# LightLog_SMD_0_7.net
KiCad netlist of a schematic drawn in EAGLE
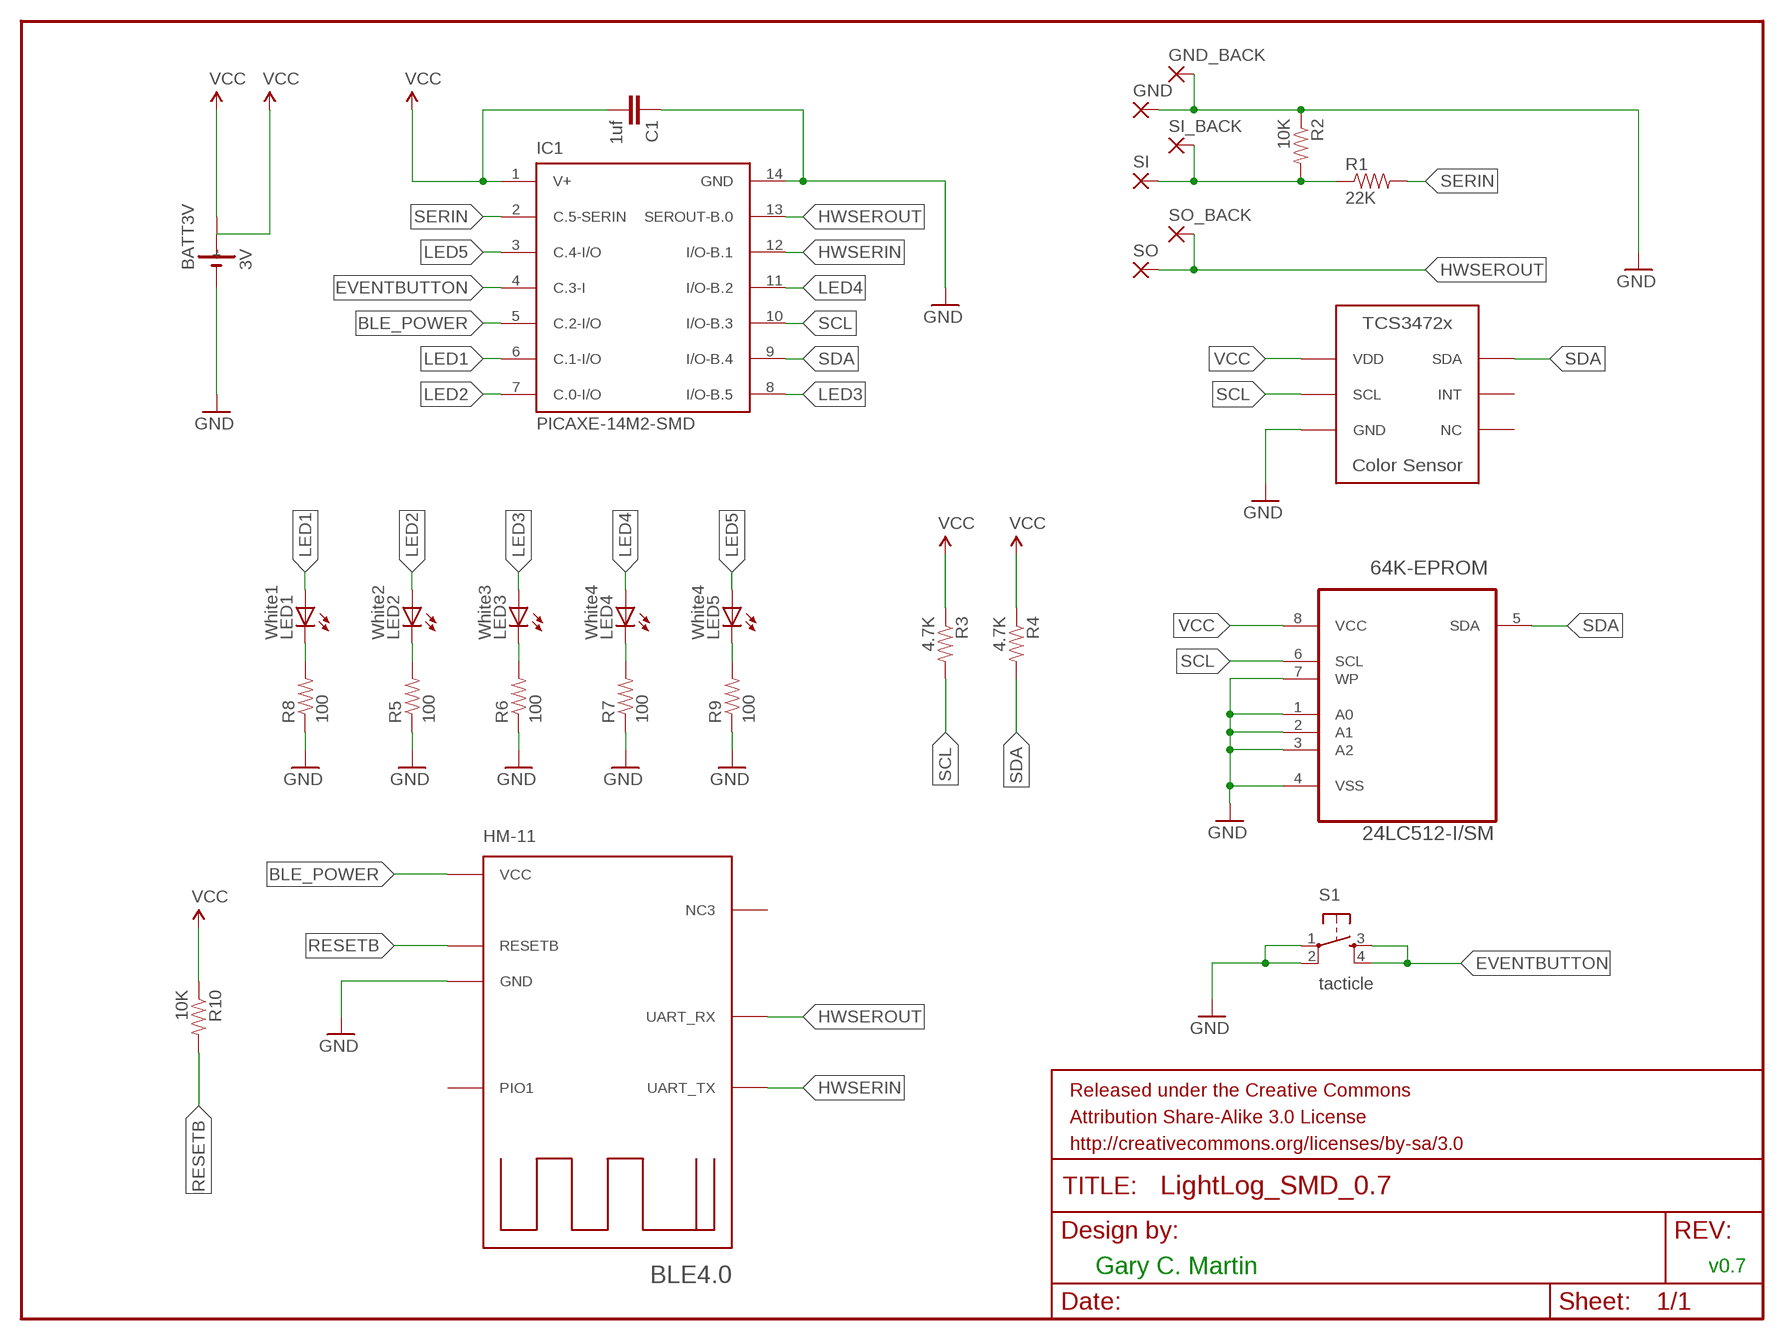
[diagram p0: schematic, sheet 1]

(export (version "E")
  (design (tool "Eeschema 10.0.6"))
  (components
    (comp (ref "64K-EPROM")
      (value "24LC512-I/SM")
      (footprint "eagle-import:SOIC127P794X203-8N")
      (libsource (lib "eagle-import") (part "24LC512-I/SM"))
    )
    (comp (ref "BATT3V")
      (value "3V")
      (footprint "eagle-import:BAT-HLD-001-CR2032-SMD")
      (libsource (lib "eagle-import") (part "BAT-HLD-001-CR2032"))
    )
    (comp (ref "BLE4.0")
      (value "HM-11")
      (footprint "eagle-import:HM-11-MIN")
      (libsource (lib "eagle-import") (part "HM-11-MIN"))
    )
    (comp (ref "C1")
      (value "1uf")
      (footprint "eagle-import:0805")
      (libsource (lib "eagle-import") (part "CAP0805"))
    )
    (comp (ref "GND")
      (value "SMD2")
      (footprint "eagle-import:SMD1,27-2,54")
      (libsource (lib "eagle-import") (part "SMD2"))
    )
    (comp (ref "GND_BACK")
      (value "SMD2")
      (footprint "eagle-import:SMD1,27-2,54")
      (libsource (lib "eagle-import") (part "SMD2"))
    )
    (comp (ref "IC1")
      (value "PICAXE-14M2-SMD")
      (footprint "eagle-import:SOIC14")
      (libsource (lib "eagle-import") (part "PICAXE-14M2-SMD"))
    )
    (comp (ref "LED1")
      (value "White1")
      (footprint "eagle-import:LED-0603")
      (libsource (lib "eagle-import") (part "LED0603"))
    )
    (comp (ref "LED2")
      (value "White2")
      (footprint "eagle-import:LED-0603")
      (libsource (lib "eagle-import") (part "LED0603"))
    )
    (comp (ref "LED3")
      (value "White3")
      (footprint "eagle-import:LED-0603")
      (libsource (lib "eagle-import") (part "LED0603"))
    )
    (comp (ref "LED4")
      (value "White4")
      (footprint "eagle-import:LED-0603")
      (libsource (lib "eagle-import") (part "LED0603"))
    )
    (comp (ref "LED5")
      (value "White4")
      (footprint "eagle-import:LED-0603")
      (libsource (lib "eagle-import") (part "LED0603"))
    )
    (comp (ref "R1")
      (value "22K")
      (footprint "eagle-import:0805")
      (libsource (lib "eagle-import") (part "RESISTOR0805-RES"))
    )
    (comp (ref "R2")
      (value "10K")
      (footprint "eagle-import:0805")
      (libsource (lib "eagle-import") (part "RESISTOR0805-RES"))
    )
    (comp (ref "R3")
      (value "4.7K")
      (footprint "eagle-import:0805")
      (libsource (lib "eagle-import") (part "RESISTOR0805-RES"))
    )
    (comp (ref "R4")
      (value "4.7K")
      (footprint "eagle-import:0805")
      (libsource (lib "eagle-import") (part "RESISTOR0805-RES"))
    )
    (comp (ref "R5")
      (value "100")
      (footprint "eagle-import:0805")
      (libsource (lib "eagle-import") (part "RESISTOR0805-RES"))
    )
    (comp (ref "R6")
      (value "100")
      (footprint "eagle-import:0805")
      (libsource (lib "eagle-import") (part "RESISTOR0805-RES"))
    )
    (comp (ref "R7")
      (value "100")
      (footprint "eagle-import:0805")
      (libsource (lib "eagle-import") (part "RESISTOR0805-RES"))
    )
    (comp (ref "R8")
      (value "100")
      (footprint "eagle-import:0805")
      (libsource (lib "eagle-import") (part "RESISTOR0805-RES"))
    )
    (comp (ref "R9")
      (value "100")
      (footprint "eagle-import:0805")
      (libsource (lib "eagle-import") (part "RESISTOR0805-RES"))
    )
    (comp (ref "R10")
      (value "10K")
      (footprint "eagle-import:0805")
      (libsource (lib "eagle-import") (part "RESISTOR0805-RES"))
    )
    (comp (ref "S1")
      (value "tacticle")
      (footprint "eagle-import:TACTILE_SWITCH_SMD")
      (libsource (lib "eagle-import") (part "TAC_SWITCHSMD"))
    )
    (comp (ref "SI")
      (value "SMD2")
      (footprint "eagle-import:SMD1,27-2,54")
      (libsource (lib "eagle-import") (part "SMD2"))
    )
    (comp (ref "SI_BACK")
      (value "SMD2")
      (footprint "eagle-import:SMD1,27-2,54")
      (libsource (lib "eagle-import") (part "SMD2"))
    )
    (comp (ref "SO")
      (value "SMD2")
      (footprint "eagle-import:SMD1,27-2,54")
      (libsource (lib "eagle-import") (part "SMD2"))
    )
    (comp (ref "SO_BACK")
      (value "SMD2")
      (footprint "eagle-import:SMD1,27-2,54")
      (libsource (lib "eagle-import") (part "SMD2"))
    )
    (comp (ref "U$1")
      (value "TCS3472")
      (footprint "eagle-import:DUAL-FLAT-NO-LEAD-6PIN")
      (libsource (lib "eagle-import") (part "TCS3472"))
    )
  )
  (nets
    (net (code "1") (name "BLE_POWER") (class "Default")
      (node (ref "BLE4.0") (pin "VCC") (pinfunction "VCC_VCC") (pintype "bidirectional"))
      (node (ref "IC1") (pin "5") (pinfunction "C.2-I/O_5") (pintype "bidirectional"))
    )
    (net (code "2") (name "EVENTBUTTON") (class "Default")
      (node (ref "IC1") (pin "4") (pinfunction "C.3-I_4") (pintype "input"))
      (node (ref "S1") (pin "3") (pinfunction "3_3") (pintype "passive"))
      (node (ref "S1") (pin "4") (pinfunction "4_4") (pintype "passive"))
    )
    (net (code "3") (name "GND") (class "Default")
      (node (ref "64K-EPROM") (pin "1") (pinfunction "A0_1") (pintype "input"))
      (node (ref "64K-EPROM") (pin "2") (pinfunction "A1_2") (pintype "input"))
      (node (ref "64K-EPROM") (pin "3") (pinfunction "A2_3") (pintype "input"))
      (node (ref "64K-EPROM") (pin "4") (pinfunction "VSS_4") (pintype "passive"))
      (node (ref "64K-EPROM") (pin "7") (pinfunction "WP_7") (pintype "input"))
      (node (ref "BATT3V") (pin "NEG") (pinfunction "-_NEG") (pintype "passive"))
      (node (ref "BLE4.0") (pin "GND") (pinfunction "GND_GND") (pintype "bidirectional"))
      (node (ref "C1") (pin "1") (pinfunction "1_1") (pintype "passive"))
      (node (ref "GND") (pin "1") (pinfunction "P_1") (pintype "passive"))
      (node (ref "GND_BACK") (pin "1") (pinfunction "P_1") (pintype "passive"))
      (node (ref "IC1") (pin "14") (pinfunction "GND_14") (pintype "power_in"))
      (node (ref "R2") (pin "1") (pinfunction "1_1") (pintype "passive"))
      (node (ref "R5") (pin "1") (pinfunction "1_1") (pintype "passive"))
      (node (ref "R6") (pin "1") (pinfunction "1_1") (pintype "passive"))
      (node (ref "R7") (pin "1") (pinfunction "1_1") (pintype "passive"))
      (node (ref "R8") (pin "1") (pinfunction "1_1") (pintype "passive"))
      (node (ref "R9") (pin "1") (pinfunction "1_1") (pintype "passive"))
      (node (ref "S1") (pin "1") (pinfunction "1_1") (pintype "passive"))
      (node (ref "S1") (pin "2") (pinfunction "2_2") (pintype "passive"))
      (node (ref "U$1") (pin "3") (pinfunction "GND_3") (pintype "bidirectional"))
    )
    (net (code "4") (name "HWSERIN") (class "Default")
      (node (ref "BLE4.0") (pin "UART_TX") (pinfunction "UART_TX_UART_TX") (pintype "bidirectional"))
      (node (ref "IC1") (pin "12") (pinfunction "I/O-B.1_12") (pintype "bidirectional"))
    )
    (net (code "5") (name "HWSEROUT") (class "Default")
      (node (ref "BLE4.0") (pin "UART_RX") (pinfunction "UART_RX_UART_RX") (pintype "bidirectional"))
      (node (ref "IC1") (pin "13") (pinfunction "SEROUT-B.0_13") (pintype "output"))
      (node (ref "SO") (pin "1") (pinfunction "P_1") (pintype "passive"))
      (node (ref "SO_BACK") (pin "1") (pinfunction "P_1") (pintype "passive"))
    )
    (net (code "6") (name "LED1") (class "Default")
      (node (ref "IC1") (pin "6") (pinfunction "C.1-I/O_6") (pintype "bidirectional"))
      (node (ref "LED1") (pin "A") (pinfunction "A_A") (pintype "passive"))
    )
    (net (code "7") (name "LED2") (class "Default")
      (node (ref "IC1") (pin "7") (pinfunction "C.0-I/O_7") (pintype "bidirectional"))
      (node (ref "LED2") (pin "A") (pinfunction "A_A") (pintype "passive"))
    )
    (net (code "8") (name "LED3") (class "Default")
      (node (ref "IC1") (pin "8") (pinfunction "I/O-B.5_8") (pintype "bidirectional"))
      (node (ref "LED3") (pin "A") (pinfunction "A_A") (pintype "passive"))
    )
    (net (code "9") (name "LED4") (class "Default")
      (node (ref "IC1") (pin "11") (pinfunction "I/O-B.2_11") (pintype "bidirectional"))
      (node (ref "LED4") (pin "A") (pinfunction "A_A") (pintype "passive"))
    )
    (net (code "10") (name "LED5") (class "Default")
      (node (ref "IC1") (pin "3") (pinfunction "C.4-I/O_3") (pintype "bidirectional"))
      (node (ref "LED5") (pin "A") (pinfunction "A_A") (pintype "passive"))
    )
    (net (code "11") (name "Net-(LED1-PadC)") (class "Default")
      (node (ref "LED1") (pin "C") (pinfunction "C_C") (pintype "passive"))
      (node (ref "R8") (pin "2") (pinfunction "2_2") (pintype "passive"))
    )
    (net (code "12") (name "Net-(LED2-PadC)") (class "Default")
      (node (ref "LED2") (pin "C") (pinfunction "C_C") (pintype "passive"))
      (node (ref "R5") (pin "2") (pinfunction "2_2") (pintype "passive"))
    )
    (net (code "13") (name "Net-(LED3-PadC)") (class "Default")
      (node (ref "LED3") (pin "C") (pinfunction "C_C") (pintype "passive"))
      (node (ref "R6") (pin "2") (pinfunction "2_2") (pintype "passive"))
    )
    (net (code "14") (name "Net-(LED4-PadC)") (class "Default")
      (node (ref "LED4") (pin "C") (pinfunction "C_C") (pintype "passive"))
      (node (ref "R7") (pin "2") (pinfunction "2_2") (pintype "passive"))
    )
    (net (code "15") (name "Net-(LED5-PadC)") (class "Default")
      (node (ref "LED5") (pin "C") (pinfunction "C_C") (pintype "passive"))
      (node (ref "R9") (pin "2") (pinfunction "2_2") (pintype "passive"))
    )
    (net (code "16") (name "Net-(SI-P)") (class "Default")
      (node (ref "R1") (pin "1") (pinfunction "1_1") (pintype "passive"))
      (node (ref "R2") (pin "2") (pinfunction "2_2") (pintype "passive"))
      (node (ref "SI") (pin "1") (pinfunction "P_1") (pintype "passive"))
      (node (ref "SI_BACK") (pin "1") (pinfunction "P_1") (pintype "passive"))
    )
    (net (code "17") (name "RESETB") (class "Default")
      (node (ref "BLE4.0") (pin "RESETB") (pinfunction "RESETB_RESETB") (pintype "bidirectional"))
      (node (ref "R10") (pin "2") (pinfunction "2_2") (pintype "passive"))
    )
    (net (code "18") (name "SCL") (class "Default")
      (node (ref "64K-EPROM") (pin "6") (pinfunction "SCL_6") (pintype "input"))
      (node (ref "IC1") (pin "10") (pinfunction "I/O-B.3_10") (pintype "bidirectional"))
      (node (ref "R3") (pin "2") (pinfunction "2_2") (pintype "passive"))
      (node (ref "U$1") (pin "2") (pinfunction "SCL_2") (pintype "bidirectional"))
    )
    (net (code "19") (name "SDA") (class "Default")
      (node (ref "64K-EPROM") (pin "5") (pinfunction "SDA_5") (pintype "bidirectional"))
      (node (ref "IC1") (pin "9") (pinfunction "I/O-B.4_9") (pintype "bidirectional"))
      (node (ref "R4") (pin "2") (pinfunction "2_2") (pintype "passive"))
      (node (ref "U$1") (pin "6") (pinfunction "SDA_6") (pintype "bidirectional"))
    )
    (net (code "20") (name "SERIN") (class "Default")
      (node (ref "IC1") (pin "2") (pinfunction "C.5-SERIN_2") (pintype "input"))
      (node (ref "R1") (pin "2") (pinfunction "2_2") (pintype "passive"))
    )
    (net (code "21") (name "VCC") (class "Default")
      (node (ref "64K-EPROM") (pin "8") (pinfunction "VCC_8") (pintype "power_in"))
      (node (ref "BATT3V") (pin "POS1") (pinfunction "+_POS1") (pintype "passive"))
      (node (ref "BATT3V") (pin "POS2") (pinfunction "+_POS2") (pintype "passive"))
      (node (ref "C1") (pin "2") (pinfunction "2_2") (pintype "passive"))
      (node (ref "IC1") (pin "1") (pinfunction "V+_1") (pintype "power_in"))
      (node (ref "R10") (pin "1") (pinfunction "1_1") (pintype "passive"))
      (node (ref "R3") (pin "1") (pinfunction "1_1") (pintype "passive"))
      (node (ref "R4") (pin "1") (pinfunction "1_1") (pintype "passive"))
      (node (ref "U$1") (pin "1") (pinfunction "VDD_1") (pintype "bidirectional"))
    )
    (net (code "22") (name "unconnected-(BLE4.0-PIO1-PadPOI1)") (class "Default")
      (node (ref "BLE4.0") (pin "POI1") (pinfunction "PIO1_POI1") (pintype "bidirectional"))
    )
    (net (code "23") (name "unconnected-(BLE4.0-PadNC3)") (class "Default")
      (node (ref "BLE4.0") (pin "NC3") (pinfunction "NC3_NC3") (pintype "bidirectional"))
    )
    (net (code "24") (name "unconnected-(U$1-INT-Pad5)") (class "Default")
      (node (ref "U$1") (pin "5") (pinfunction "INT_5") (pintype "bidirectional"))
    )
    (net (code "25") (name "unconnected-(U$1-NC-Pad4)") (class "Default")
      (node (ref "U$1") (pin "4") (pinfunction "NC_4") (pintype "bidirectional"))
    )
  )
)
